# Sheet2.net
KiCad netlist of a schematic drawn in Altium Designer
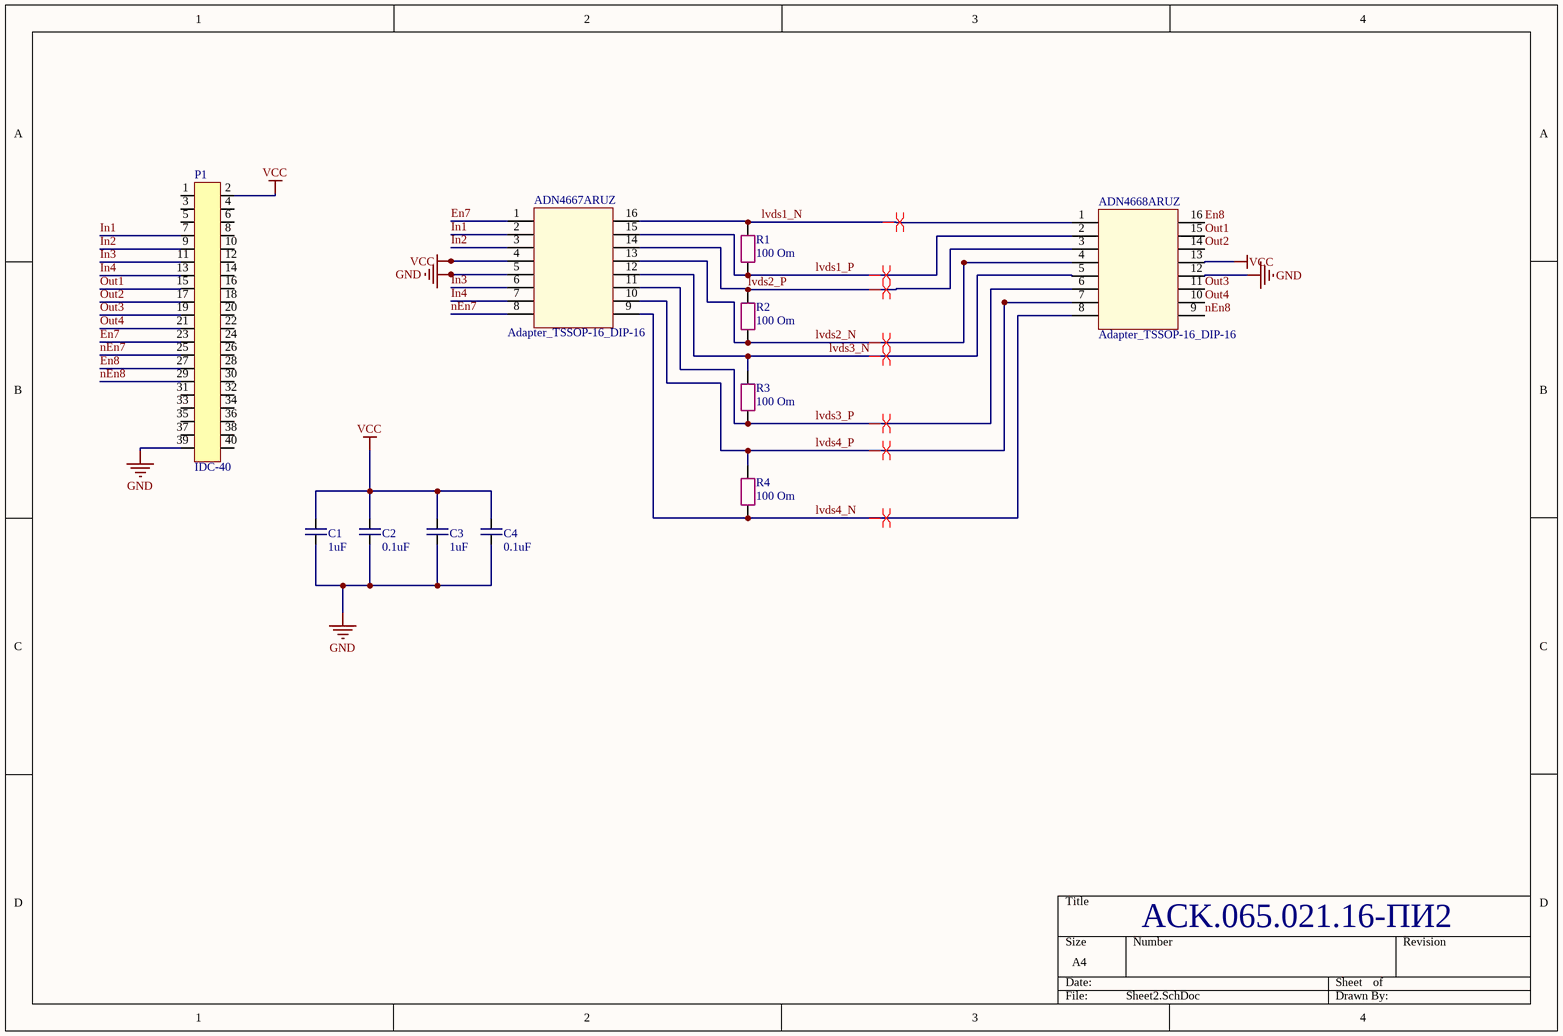
[diagram p0: Sheet2.SchDoc]

(export (version "E")
  (design (tool "Eeschema 10.0.6"))
  (components
    (comp (ref "ADN4667ARUZ")
      (value "Adapter_TSSOP-16_DIP-16")
      (footprint "Adapter_TSSOP-16_DIP-16")
      (libsource (lib "RCU") (part "Adapter_TSSOP-16_DIP-16"))
    )
    (comp (ref "ADN4668ARUZ")
      (value "Adapter_TSSOP-16_DIP-16")
      (footprint "Adapter_TSSOP-16_DIP-16")
      (libsource (lib "RCU") (part "Adapter_TSSOP-16_DIP-16"))
    )
    (comp (ref "C1") (value "1uF") (footprint "RCU:C_0805") (libsource (lib "RCU") (part "capacitor 0805")))
    (comp (ref "C2") (value "0.1uF") (footprint "RCU:C_0805") (libsource (lib "RCU") (part "capacitor 0805")))
    (comp (ref "C3") (value "1uF") (footprint "RCU:C_0805") (libsource (lib "RCU") (part "capacitor 0805")))
    (comp (ref "C4") (value "0.1uF") (footprint "RCU:C_0805") (libsource (lib "RCU") (part "capacitor 0805")))
    (comp (ref "P1")
      (value "IDC-40")
      (footprint "IDC-40")
      (description "разъем 2529")
      (libsource (lib "RCU") (part "IDC-40"))
    )
    (comp (ref "R1") (value "100 Om") (footprint "RCU:R_0805") (libsource (lib "RCU") (part "resistor 0805")))
    (comp (ref "R2") (value "100 Om") (footprint "RCU:R_0805") (libsource (lib "RCU") (part "resistor 0805")))
    (comp (ref "R3") (value "100 Om") (footprint "RCU:R_0805") (libsource (lib "RCU") (part "resistor 0805")))
    (comp (ref "R4") (value "100 Om") (footprint "RCU:R_0805") (libsource (lib "RCU") (part "resistor 0805")))
  )
  (nets
    (net (code "1") (name "/En7") (class "Default")
      (node (ref "ADN4667ARUZ") (pin "1") (pinfunction "101_1") (pintype "passive"))
      (node (ref "P1") (pin "23") (pinfunction "23_23") (pintype "passive"))
    )
    (net (code "2") (name "/En8") (class "Default")
      (node (ref "ADN4668ARUZ") (pin "16") (pinfunction "116_16") (pintype "passive"))
      (node (ref "P1") (pin "27") (pinfunction "27_27") (pintype "passive"))
    )
    (net (code "3") (name "/In1") (class "Default")
      (node (ref "ADN4667ARUZ") (pin "2") (pinfunction "102_2") (pintype "passive"))
      (node (ref "P1") (pin "7") (pinfunction "7_7") (pintype "passive"))
    )
    (net (code "4") (name "/In2") (class "Default")
      (node (ref "ADN4667ARUZ") (pin "3") (pinfunction "103_3") (pintype "passive"))
      (node (ref "P1") (pin "9") (pinfunction "9_9") (pintype "passive"))
    )
    (net (code "5") (name "/In3") (class "Default")
      (node (ref "ADN4667ARUZ") (pin "6") (pinfunction "106_6") (pintype "passive"))
      (node (ref "P1") (pin "11") (pinfunction "11_11") (pintype "passive"))
    )
    (net (code "6") (name "/In4") (class "Default")
      (node (ref "ADN4667ARUZ") (pin "7") (pinfunction "107_7") (pintype "passive"))
      (node (ref "P1") (pin "13") (pinfunction "13_13") (pintype "passive"))
    )
    (net (code "7") (name "/Out1") (class "Default")
      (node (ref "ADN4668ARUZ") (pin "15") (pinfunction "115_15") (pintype "passive"))
      (node (ref "P1") (pin "15") (pinfunction "15_15") (pintype "passive"))
    )
    (net (code "8") (name "/Out2") (class "Default")
      (node (ref "ADN4668ARUZ") (pin "14") (pinfunction "114_14") (pintype "passive"))
      (node (ref "P1") (pin "17") (pinfunction "17_17") (pintype "passive"))
    )
    (net (code "9") (name "/Out3") (class "Default")
      (node (ref "ADN4668ARUZ") (pin "11") (pinfunction "111_11") (pintype "passive"))
      (node (ref "P1") (pin "19") (pinfunction "19_19") (pintype "passive"))
    )
    (net (code "10") (name "/Out4") (class "Default")
      (node (ref "ADN4668ARUZ") (pin "10") (pinfunction "110_10") (pintype "passive"))
      (node (ref "P1") (pin "21") (pinfunction "21_21") (pintype "passive"))
    )
    (net (code "11") (name "/lvds1_N") (class "Default")
      (node (ref "ADN4667ARUZ") (pin "16") (pinfunction "116_16") (pintype "passive"))
      (node (ref "ADN4668ARUZ") (pin "1") (pinfunction "101_1") (pintype "passive"))
      (node (ref "R1") (pin "2") (pinfunction "2_2") (pintype "passive"))
    )
    (net (code "12") (name "/lvds1_P") (class "Default")
      (node (ref "ADN4667ARUZ") (pin "15") (pinfunction "115_15") (pintype "passive"))
      (node (ref "ADN4668ARUZ") (pin "2") (pinfunction "102_2") (pintype "passive"))
      (node (ref "R1") (pin "1") (pinfunction "1_1") (pintype "passive"))
    )
    (net (code "13") (name "/lvds2_N") (class "Default")
      (node (ref "ADN4667ARUZ") (pin "13") (pinfunction "113_13") (pintype "passive"))
      (node (ref "ADN4668ARUZ") (pin "4") (pinfunction "104_4") (pintype "passive"))
      (node (ref "R2") (pin "1") (pinfunction "1_1") (pintype "passive"))
    )
    (net (code "14") (name "/lvds2_P") (class "Default")
      (node (ref "ADN4667ARUZ") (pin "14") (pinfunction "114_14") (pintype "passive"))
      (node (ref "ADN4668ARUZ") (pin "3") (pinfunction "103_3") (pintype "passive"))
      (node (ref "R2") (pin "2") (pinfunction "2_2") (pintype "passive"))
    )
    (net (code "15") (name "/lvds3_N") (class "Default")
      (node (ref "ADN4667ARUZ") (pin "12") (pinfunction "112_12") (pintype "passive"))
      (node (ref "ADN4668ARUZ") (pin "5") (pinfunction "105_5") (pintype "passive"))
      (node (ref "R3") (pin "2") (pinfunction "2_2") (pintype "passive"))
    )
    (net (code "16") (name "/lvds3_P") (class "Default")
      (node (ref "ADN4667ARUZ") (pin "11") (pinfunction "111_11") (pintype "passive"))
      (node (ref "ADN4668ARUZ") (pin "6") (pinfunction "106_6") (pintype "passive"))
      (node (ref "R3") (pin "1") (pinfunction "1_1") (pintype "passive"))
    )
    (net (code "17") (name "/lvds4_N") (class "Default")
      (node (ref "ADN4667ARUZ") (pin "9") (pinfunction "109_9") (pintype "passive"))
      (node (ref "ADN4668ARUZ") (pin "8") (pinfunction "108_8") (pintype "passive"))
      (node (ref "R4") (pin "1") (pinfunction "1_1") (pintype "passive"))
    )
    (net (code "18") (name "/lvds4_P") (class "Default")
      (node (ref "ADN4667ARUZ") (pin "10") (pinfunction "110_10") (pintype "passive"))
      (node (ref "ADN4668ARUZ") (pin "7") (pinfunction "107_7") (pintype "passive"))
      (node (ref "R4") (pin "2") (pinfunction "2_2") (pintype "passive"))
    )
    (net (code "19") (name "/nEn7") (class "Default")
      (node (ref "ADN4667ARUZ") (pin "8") (pinfunction "108_8") (pintype "passive"))
      (node (ref "P1") (pin "25") (pinfunction "25_25") (pintype "passive"))
    )
    (net (code "20") (name "/nEn8") (class "Default")
      (node (ref "ADN4668ARUZ") (pin "9") (pinfunction "109_9") (pintype "passive"))
      (node (ref "P1") (pin "29") (pinfunction "29_29") (pintype "passive"))
    )
    (net (code "21") (name "GND") (class "Default")
      (node (ref "ADN4667ARUZ") (pin "5") (pinfunction "105_5") (pintype "passive"))
      (node (ref "ADN4668ARUZ") (pin "12") (pinfunction "112_12") (pintype "passive"))
      (node (ref "C1") (pin "2") (pinfunction "2_2") (pintype "passive"))
      (node (ref "C2") (pin "2") (pinfunction "2_2") (pintype "passive"))
      (node (ref "C3") (pin "2") (pinfunction "2_2") (pintype "passive"))
      (node (ref "C4") (pin "2") (pinfunction "2_2") (pintype "passive"))
      (node (ref "P1") (pin "39") (pinfunction "39_39") (pintype "passive"))
    )
    (net (code "22") (name "VCC") (class "Default")
      (node (ref "ADN4667ARUZ") (pin "4") (pinfunction "104_4") (pintype "passive"))
      (node (ref "ADN4668ARUZ") (pin "13") (pinfunction "113_13") (pintype "passive"))
      (node (ref "C1") (pin "1") (pinfunction "1_1") (pintype "passive"))
      (node (ref "C2") (pin "1") (pinfunction "1_1") (pintype "passive"))
      (node (ref "C3") (pin "1") (pinfunction "1_1") (pintype "passive"))
      (node (ref "C4") (pin "1") (pinfunction "1_1") (pintype "passive"))
      (node (ref "P1") (pin "2") (pinfunction "2_2") (pintype "passive"))
    )
    (net (code "23") (name "unconnected-(P1-0-Pad1)") (class "Default")
      (node (ref "P1") (pin "1") (pinfunction "0_1") (pintype "passive"))
    )
    (net (code "24") (name "unconnected-(P1-Pad3)") (class "Default")
      (node (ref "P1") (pin "3") (pinfunction "3_3") (pintype "passive"))
    )
    (net (code "25") (name "unconnected-(P1-Pad4)") (class "Default")
      (node (ref "P1") (pin "4") (pinfunction "4_4") (pintype "passive"))
    )
    (net (code "26") (name "unconnected-(P1-Pad5)") (class "Default")
      (node (ref "P1") (pin "5") (pinfunction "5_5") (pintype "passive"))
    )
    (net (code "27") (name "unconnected-(P1-Pad6)") (class "Default")
      (node (ref "P1") (pin "6") (pinfunction "6_6") (pintype "passive"))
    )
    (net (code "28") (name "unconnected-(P1-Pad8)") (class "Default")
      (node (ref "P1") (pin "8") (pinfunction "8_8") (pintype "passive"))
    )
    (net (code "29") (name "unconnected-(P1-Pad10)") (class "Default")
      (node (ref "P1") (pin "10") (pinfunction "10_10") (pintype "passive"))
    )
    (net (code "30") (name "unconnected-(P1-Pad12)") (class "Default")
      (node (ref "P1") (pin "12") (pinfunction "12_12") (pintype "passive"))
    )
    (net (code "31") (name "unconnected-(P1-Pad14)") (class "Default")
      (node (ref "P1") (pin "14") (pinfunction "14_14") (pintype "passive"))
    )
    (net (code "32") (name "unconnected-(P1-Pad16)") (class "Default")
      (node (ref "P1") (pin "16") (pinfunction "16_16") (pintype "passive"))
    )
    (net (code "33") (name "unconnected-(P1-Pad18)") (class "Default")
      (node (ref "P1") (pin "18") (pinfunction "18_18") (pintype "passive"))
    )
    (net (code "34") (name "unconnected-(P1-Pad20)") (class "Default")
      (node (ref "P1") (pin "20") (pinfunction "20_20") (pintype "passive"))
    )
    (net (code "35") (name "unconnected-(P1-Pad22)") (class "Default")
      (node (ref "P1") (pin "22") (pinfunction "22_22") (pintype "passive"))
    )
    (net (code "36") (name "unconnected-(P1-Pad24)") (class "Default")
      (node (ref "P1") (pin "24") (pinfunction "24_24") (pintype "passive"))
    )
    (net (code "37") (name "unconnected-(P1-Pad26)") (class "Default")
      (node (ref "P1") (pin "26") (pinfunction "26_26") (pintype "passive"))
    )
    (net (code "38") (name "unconnected-(P1-Pad28)") (class "Default")
      (node (ref "P1") (pin "28") (pinfunction "28_28") (pintype "passive"))
    )
    (net (code "39") (name "unconnected-(P1-Pad30)") (class "Default")
      (node (ref "P1") (pin "30") (pinfunction "30_30") (pintype "passive"))
    )
    (net (code "40") (name "unconnected-(P1-Pad31)") (class "Default")
      (node (ref "P1") (pin "31") (pinfunction "31_31") (pintype "passive"))
    )
    (net (code "41") (name "unconnected-(P1-Pad32)") (class "Default")
      (node (ref "P1") (pin "32") (pinfunction "32_32") (pintype "passive"))
    )
    (net (code "42") (name "unconnected-(P1-Pad33)") (class "Default")
      (node (ref "P1") (pin "33") (pinfunction "33_33") (pintype "passive"))
    )
    (net (code "43") (name "unconnected-(P1-Pad34)") (class "Default")
      (node (ref "P1") (pin "34") (pinfunction "34_34") (pintype "passive"))
    )
    (net (code "44") (name "unconnected-(P1-Pad35)") (class "Default")
      (node (ref "P1") (pin "35") (pinfunction "35_35") (pintype "passive"))
    )
    (net (code "45") (name "unconnected-(P1-Pad36)") (class "Default")
      (node (ref "P1") (pin "36") (pinfunction "36_36") (pintype "passive"))
    )
    (net (code "46") (name "unconnected-(P1-Pad37)") (class "Default")
      (node (ref "P1") (pin "37") (pinfunction "37_37") (pintype "passive"))
    )
    (net (code "47") (name "unconnected-(P1-Pad38)") (class "Default")
      (node (ref "P1") (pin "38") (pinfunction "38_38") (pintype "passive"))
    )
    (net (code "48") (name "unconnected-(P1-Pad40)") (class "Default")
      (node (ref "P1") (pin "40") (pinfunction "40_40") (pintype "passive"))
    )
  )
)
